# Number.net
KiCad netlist of a schematic drawn in EAGLE
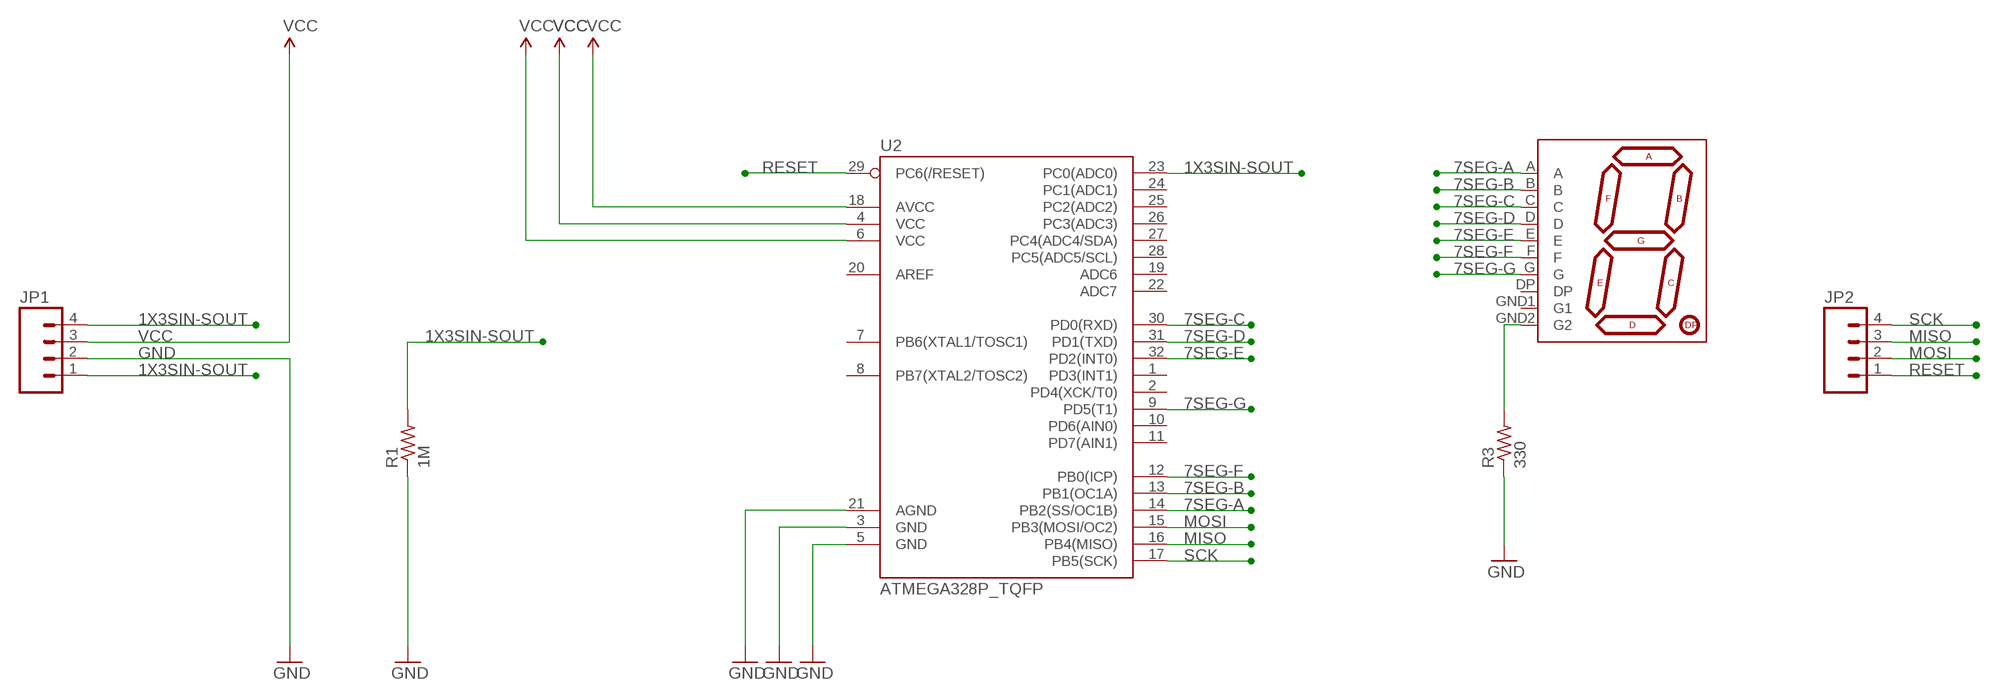
[diagram p0: schematic, sheet 1]

(export (version "E")
  (design (tool "Eeschema 10.0.6"))
  (components
    (comp (ref "JP1")
      (value "M04PTH")
      (footprint "eagle-import:1X04")
      (libsource (lib "eagle-import") (part "M04PTH"))
    )
    (comp (ref "JP2")
      (value "M04PTH")
      (footprint "eagle-import:1X04")
      (libsource (lib "eagle-import") (part "M04PTH"))
    )
    (comp (ref "R1")
      (value "1M")
      (footprint "eagle-import:R0603")
      (libsource (lib "eagle-import") (part "R-US_R0603"))
    )
    (comp (ref "R3")
      (value "330")
      (footprint "eagle-import:R0603")
      (libsource (lib "eagle-import") (part "resistor_R-US_R0603"))
    )
    (comp (ref "U$1")
      (value "7SEGMENT")
      (footprint "eagle-import:7SEG-SMD-10X7.3")
      (libsource (lib "eagle-import") (part "7SEGMENT"))
    )
    (comp (ref "U2")
      (value "ATMEGA328P_TQFP")
      (footprint "eagle-import:TQFP32-08")
      (libsource (lib "eagle-import") (part "ATMEGA328P_TQFP"))
    )
  )
  (nets
    (net (code "1") (name "/1X3SIN-SOUT") (class "Default")
      (node (ref "JP1") (pin "1") (pinfunction "1_1") (pintype "passive"))
      (node (ref "JP1") (pin "4") (pinfunction "4_4") (pintype "passive"))
      (node (ref "R1") (pin "2") (pinfunction "2_2") (pintype "passive"))
      (node (ref "U2") (pin "23") (pinfunction "PC0(ADC0)_23") (pintype "bidirectional"))
    )
    (net (code "2") (name "/7SEG-A") (class "Default")
      (node (ref "U$1") (pin "A") (pinfunction "A_A") (pintype "bidirectional"))
      (node (ref "U2") (pin "14") (pinfunction "PB2(SS/OC1B)_14") (pintype "bidirectional"))
    )
    (net (code "3") (name "/7SEG-B") (class "Default")
      (node (ref "U$1") (pin "B") (pinfunction "B_B") (pintype "bidirectional"))
      (node (ref "U2") (pin "13") (pinfunction "PB1(OC1A)_13") (pintype "bidirectional"))
    )
    (net (code "4") (name "/7SEG-C") (class "Default")
      (node (ref "U$1") (pin "C") (pinfunction "C_C") (pintype "bidirectional"))
      (node (ref "U2") (pin "30") (pinfunction "PD0(RXD)_30") (pintype "bidirectional"))
    )
    (net (code "5") (name "/7SEG-D") (class "Default")
      (node (ref "U$1") (pin "D") (pinfunction "D_D") (pintype "bidirectional"))
      (node (ref "U2") (pin "31") (pinfunction "PD1(TXD)_31") (pintype "bidirectional"))
    )
    (net (code "6") (name "/7SEG-E") (class "Default")
      (node (ref "U$1") (pin "E") (pinfunction "E_E") (pintype "bidirectional"))
      (node (ref "U2") (pin "32") (pinfunction "PD2(INT0)_32") (pintype "bidirectional"))
    )
    (net (code "7") (name "/7SEG-F") (class "Default")
      (node (ref "U$1") (pin "F") (pinfunction "F_F") (pintype "bidirectional"))
      (node (ref "U2") (pin "12") (pinfunction "PB0(ICP)_12") (pintype "bidirectional"))
    )
    (net (code "8") (name "/7SEG-G") (class "Default")
      (node (ref "U$1") (pin "G") (pinfunction "G_G") (pintype "bidirectional"))
      (node (ref "U2") (pin "9") (pinfunction "PD5(T1)_9") (pintype "bidirectional"))
    )
    (net (code "9") (name "/MISO") (class "Default")
      (node (ref "JP2") (pin "3") (pinfunction "3_3") (pintype "passive"))
      (node (ref "U2") (pin "16") (pinfunction "PB4(MISO)_16") (pintype "bidirectional"))
    )
    (net (code "10") (name "/MOSI") (class "Default")
      (node (ref "JP2") (pin "2") (pinfunction "2_2") (pintype "passive"))
      (node (ref "U2") (pin "15") (pinfunction "PB3(MOSI/OC2)_15") (pintype "bidirectional"))
    )
    (net (code "11") (name "/RESET") (class "Default")
      (node (ref "JP2") (pin "1") (pinfunction "1_1") (pintype "passive"))
      (node (ref "U2") (pin "29") (pinfunction "PC6(/RESET)_29") (pintype "bidirectional"))
    )
    (net (code "12") (name "/SCK") (class "Default")
      (node (ref "JP2") (pin "4") (pinfunction "4_4") (pintype "passive"))
      (node (ref "U2") (pin "17") (pinfunction "PB5(SCK)_17") (pintype "bidirectional"))
    )
    (net (code "13") (name "GND") (class "Default")
      (node (ref "JP1") (pin "2") (pinfunction "2_2") (pintype "passive"))
      (node (ref "R1") (pin "1") (pinfunction "1_1") (pintype "passive"))
      (node (ref "R3") (pin "1") (pinfunction "1_1") (pintype "passive"))
      (node (ref "U2") (pin "21") (pinfunction "AGND_21") (pintype "bidirectional"))
      (node (ref "U2") (pin "3") (pinfunction "GND_3") (pintype "bidirectional"))
      (node (ref "U2") (pin "5") (pinfunction "GND_5") (pintype "bidirectional"))
    )
    (net (code "14") (name "Net-(U$1-G2)") (class "Default")
      (node (ref "R3") (pin "2") (pinfunction "2_2") (pintype "passive"))
      (node (ref "U$1") (pin "GND2") (pinfunction "G2_GND2") (pintype "bidirectional"))
    )
    (net (code "15") (name "VCC") (class "Default")
      (node (ref "JP1") (pin "3") (pinfunction "3_3") (pintype "passive"))
      (node (ref "U2") (pin "18") (pinfunction "AVCC_18") (pintype "bidirectional"))
      (node (ref "U2") (pin "4") (pinfunction "VCC_4") (pintype "bidirectional"))
      (node (ref "U2") (pin "6") (pinfunction "VCC_6") (pintype "bidirectional"))
    )
    (net (code "16") (name "unconnected-(U$1-G1-PadGND1)") (class "Default")
      (node (ref "U$1") (pin "GND1") (pinfunction "G1_GND1") (pintype "bidirectional"))
    )
    (net (code "17") (name "unconnected-(U$1-PadDP)") (class "Default")
      (node (ref "U$1") (pin "DP") (pinfunction "DP_DP") (pintype "bidirectional"))
    )
    (net (code "18") (name "unconnected-(U2-ADC6-Pad19)") (class "Default")
      (node (ref "U2") (pin "19") (pinfunction "ADC6_19") (pintype "bidirectional"))
    )
    (net (code "19") (name "unconnected-(U2-ADC7-Pad22)") (class "Default")
      (node (ref "U2") (pin "22") (pinfunction "ADC7_22") (pintype "bidirectional"))
    )
    (net (code "20") (name "unconnected-(U2-AREF-Pad20)") (class "Default")
      (node (ref "U2") (pin "20") (pinfunction "AREF_20") (pintype "bidirectional"))
    )
    (net (code "21") (name "unconnected-(U2-PB6(XTAL1{slash}TOSC1)-Pad7)") (class "Default")
      (node (ref "U2") (pin "7") (pinfunction "PB6(XTAL1/TOSC1)_7") (pintype "bidirectional"))
    )
    (net (code "22") (name "unconnected-(U2-PB7(XTAL2{slash}TOSC2)-Pad8)") (class "Default")
      (node (ref "U2") (pin "8") (pinfunction "PB7(XTAL2/TOSC2)_8") (pintype "bidirectional"))
    )
    (net (code "23") (name "unconnected-(U2-PC1(ADC1)-Pad24)") (class "Default")
      (node (ref "U2") (pin "24") (pinfunction "PC1(ADC1)_24") (pintype "bidirectional"))
    )
    (net (code "24") (name "unconnected-(U2-PC2(ADC2)-Pad25)") (class "Default")
      (node (ref "U2") (pin "25") (pinfunction "PC2(ADC2)_25") (pintype "bidirectional"))
    )
    (net (code "25") (name "unconnected-(U2-PC3(ADC3)-Pad26)") (class "Default")
      (node (ref "U2") (pin "26") (pinfunction "PC3(ADC3)_26") (pintype "bidirectional"))
    )
    (net (code "26") (name "unconnected-(U2-PC4(ADC4{slash}SDA)-Pad27)") (class "Default")
      (node (ref "U2") (pin "27") (pinfunction "PC4(ADC4/SDA)_27") (pintype "bidirectional"))
    )
    (net (code "27") (name "unconnected-(U2-PC5(ADC5{slash}SCL)-Pad28)") (class "Default")
      (node (ref "U2") (pin "28") (pinfunction "PC5(ADC5/SCL)_28") (pintype "bidirectional"))
    )
    (net (code "28") (name "unconnected-(U2-PD3(INT1)-Pad1)") (class "Default")
      (node (ref "U2") (pin "1") (pinfunction "PD3(INT1)_1") (pintype "bidirectional"))
    )
    (net (code "29") (name "unconnected-(U2-PD4(XCK{slash}T0)-Pad2)") (class "Default")
      (node (ref "U2") (pin "2") (pinfunction "PD4(XCK/T0)_2") (pintype "bidirectional"))
    )
    (net (code "30") (name "unconnected-(U2-PD6(AIN0)-Pad10)") (class "Default")
      (node (ref "U2") (pin "10") (pinfunction "PD6(AIN0)_10") (pintype "bidirectional"))
    )
    (net (code "31") (name "unconnected-(U2-PD7(AIN1)-Pad11)") (class "Default")
      (node (ref "U2") (pin "11") (pinfunction "PD7(AIN1)_11") (pintype "bidirectional"))
    )
  )
)
